# Sheet1.net
KiCad netlist of a schematic drawn in Altium Designer
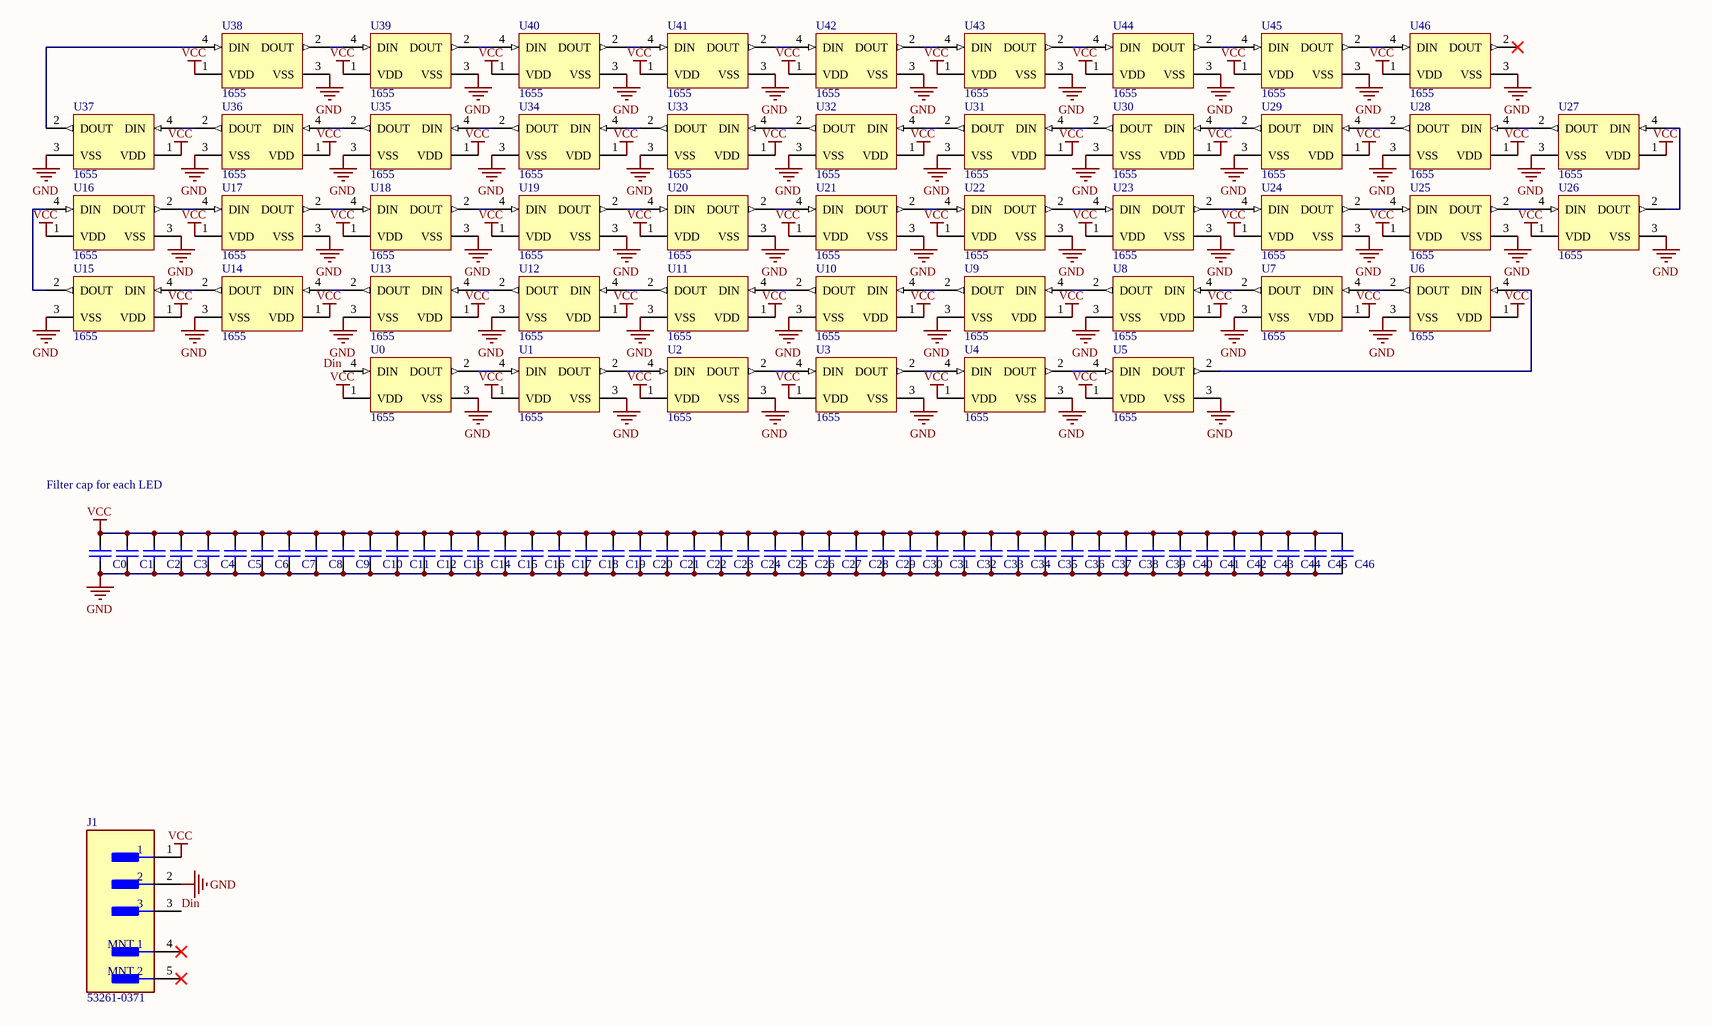
[diagram p0: Sheet1.SchDoc]

(export (version "E")
  (design (tool "Eeschema 10.0.6"))
  (components
    (comp (ref "C0")
      (value "VJ0603Y104JXJAC")
      (footprint "CAPC1608X92X38LL15T08")
      (fields (field (name "MANUFACTURER") "Vitramon"))
      (libsource (lib "Altium Content Vault") (part "CAP"))
    )
    (comp (ref "C1")
      (value "VJ0603Y104JXJAC")
      (footprint "CAPC1608X92X38LL15T08")
      (fields (field (name "MANUFACTURER") "Vitramon"))
      (libsource (lib "Altium Content Vault") (part "CAP"))
    )
    (comp (ref "C2")
      (value "VJ0603Y104JXJAC")
      (footprint "CAPC1608X92X38LL15T08")
      (fields (field (name "MANUFACTURER") "Vitramon"))
      (libsource (lib "Altium Content Vault") (part "CAP"))
    )
    (comp (ref "C3")
      (value "VJ0603Y104JXJAC")
      (footprint "CAPC1608X92X38LL15T08")
      (fields (field (name "MANUFACTURER") "Vitramon"))
      (libsource (lib "Altium Content Vault") (part "CAP"))
    )
    (comp (ref "C4")
      (value "VJ0603Y104JXJAC")
      (footprint "CAPC1608X92X38LL15T08")
      (fields (field (name "MANUFACTURER") "Vitramon"))
      (libsource (lib "Altium Content Vault") (part "CAP"))
    )
    (comp (ref "C5")
      (value "VJ0603Y104JXJAC")
      (footprint "CAPC1608X92X38LL15T08")
      (fields (field (name "MANUFACTURER") "Vitramon"))
      (libsource (lib "Altium Content Vault") (part "CAP"))
    )
    (comp (ref "C6")
      (value "VJ0603Y104JXJAC")
      (footprint "CAPC1608X92X38LL15T08")
      (fields (field (name "MANUFACTURER") "Vitramon"))
      (libsource (lib "Altium Content Vault") (part "CAP"))
    )
    (comp (ref "C7")
      (value "VJ0603Y104JXJAC")
      (footprint "CAPC1608X92X38LL15T08")
      (fields (field (name "MANUFACTURER") "Vitramon"))
      (libsource (lib "Altium Content Vault") (part "CAP"))
    )
    (comp (ref "C8")
      (value "VJ0603Y104JXJAC")
      (footprint "CAPC1608X92X38LL15T08")
      (fields (field (name "MANUFACTURER") "Vitramon"))
      (libsource (lib "Altium Content Vault") (part "CAP"))
    )
    (comp (ref "C9")
      (value "VJ0603Y104JXJAC")
      (footprint "CAPC1608X92X38LL15T08")
      (fields (field (name "MANUFACTURER") "Vitramon"))
      (libsource (lib "Altium Content Vault") (part "CAP"))
    )
    (comp (ref "C10")
      (value "VJ0603Y104JXJAC")
      (footprint "CAPC1608X92X38LL15T08")
      (fields (field (name "MANUFACTURER") "Vitramon"))
      (libsource (lib "Altium Content Vault") (part "CAP"))
    )
    (comp (ref "C11")
      (value "VJ0603Y104JXJAC")
      (footprint "CAPC1608X92X38LL15T08")
      (fields (field (name "MANUFACTURER") "Vitramon"))
      (libsource (lib "Altium Content Vault") (part "CAP"))
    )
    (comp (ref "C12")
      (value "VJ0603Y104JXJAC")
      (footprint "CAPC1608X92X38LL15T08")
      (fields (field (name "MANUFACTURER") "Vitramon"))
      (libsource (lib "Altium Content Vault") (part "CAP"))
    )
    (comp (ref "C13")
      (value "VJ0603Y104JXJAC")
      (footprint "CAPC1608X92X38LL15T08")
      (fields (field (name "MANUFACTURER") "Vitramon"))
      (libsource (lib "Altium Content Vault") (part "CAP"))
    )
    (comp (ref "C14")
      (value "VJ0603Y104JXJAC")
      (footprint "CAPC1608X92X38LL15T08")
      (fields (field (name "MANUFACTURER") "Vitramon"))
      (libsource (lib "Altium Content Vault") (part "CAP"))
    )
    (comp (ref "C15")
      (value "VJ0603Y104JXJAC")
      (footprint "CAPC1608X92X38LL15T08")
      (fields (field (name "MANUFACTURER") "Vitramon"))
      (libsource (lib "Altium Content Vault") (part "CAP"))
    )
    (comp (ref "C16")
      (value "VJ0603Y104JXJAC")
      (footprint "CAPC1608X92X38LL15T08")
      (fields (field (name "MANUFACTURER") "Vitramon"))
      (libsource (lib "Altium Content Vault") (part "CAP"))
    )
    (comp (ref "C17")
      (value "VJ0603Y104JXJAC")
      (footprint "CAPC1608X92X38LL15T08")
      (fields (field (name "MANUFACTURER") "Vitramon"))
      (libsource (lib "Altium Content Vault") (part "CAP"))
    )
    (comp (ref "C18")
      (value "VJ0603Y104JXJAC")
      (footprint "CAPC1608X92X38LL15T08")
      (fields (field (name "MANUFACTURER") "Vitramon"))
      (libsource (lib "Altium Content Vault") (part "CAP"))
    )
    (comp (ref "C19")
      (value "VJ0603Y104JXJAC")
      (footprint "CAPC1608X92X38LL15T08")
      (fields (field (name "MANUFACTURER") "Vitramon"))
      (libsource (lib "Altium Content Vault") (part "CAP"))
    )
    (comp (ref "C20")
      (value "VJ0603Y104JXJAC")
      (footprint "CAPC1608X92X38LL15T08")
      (fields (field (name "MANUFACTURER") "Vitramon"))
      (libsource (lib "Altium Content Vault") (part "CAP"))
    )
    (comp (ref "C21")
      (value "VJ0603Y104JXJAC")
      (footprint "CAPC1608X92X38LL15T08")
      (fields (field (name "MANUFACTURER") "Vitramon"))
      (libsource (lib "Altium Content Vault") (part "CAP"))
    )
    (comp (ref "C22")
      (value "VJ0603Y104JXJAC")
      (footprint "CAPC1608X92X38LL15T08")
      (fields (field (name "MANUFACTURER") "Vitramon"))
      (libsource (lib "Altium Content Vault") (part "CAP"))
    )
    (comp (ref "C23")
      (value "VJ0603Y104JXJAC")
      (footprint "CAPC1608X92X38LL15T08")
      (fields (field (name "MANUFACTURER") "Vitramon"))
      (libsource (lib "Altium Content Vault") (part "CAP"))
    )
    (comp (ref "C24")
      (value "VJ0603Y104JXJAC")
      (footprint "CAPC1608X92X38LL15T08")
      (fields (field (name "MANUFACTURER") "Vitramon"))
      (libsource (lib "Altium Content Vault") (part "CAP"))
    )
    (comp (ref "C25")
      (value "VJ0603Y104JXJAC")
      (footprint "CAPC1608X92X38LL15T08")
      (fields (field (name "MANUFACTURER") "Vitramon"))
      (libsource (lib "Altium Content Vault") (part "CAP"))
    )
    (comp (ref "C26")
      (value "VJ0603Y104JXJAC")
      (footprint "CAPC1608X92X38LL15T08")
      (fields (field (name "MANUFACTURER") "Vitramon"))
      (libsource (lib "Altium Content Vault") (part "CAP"))
    )
    (comp (ref "C27")
      (value "VJ0603Y104JXJAC")
      (footprint "CAPC1608X92X38LL15T08")
      (fields (field (name "MANUFACTURER") "Vitramon"))
      (libsource (lib "Altium Content Vault") (part "CAP"))
    )
    (comp (ref "C28")
      (value "VJ0603Y104JXJAC")
      (footprint "CAPC1608X92X38LL15T08")
      (fields (field (name "MANUFACTURER") "Vitramon"))
      (libsource (lib "Altium Content Vault") (part "CAP"))
    )
    (comp (ref "C29")
      (value "VJ0603Y104JXJAC")
      (footprint "CAPC1608X92X38LL15T08")
      (fields (field (name "MANUFACTURER") "Vitramon"))
      (libsource (lib "Altium Content Vault") (part "CAP"))
    )
    (comp (ref "C30")
      (value "VJ0603Y104JXJAC")
      (footprint "CAPC1608X92X38LL15T08")
      (fields (field (name "MANUFACTURER") "Vitramon"))
      (libsource (lib "Altium Content Vault") (part "CAP"))
    )
    (comp (ref "C31")
      (value "VJ0603Y104JXJAC")
      (footprint "CAPC1608X92X38LL15T08")
      (fields (field (name "MANUFACTURER") "Vitramon"))
      (libsource (lib "Altium Content Vault") (part "CAP"))
    )
    (comp (ref "C32")
      (value "VJ0603Y104JXJAC")
      (footprint "CAPC1608X92X38LL15T08")
      (fields (field (name "MANUFACTURER") "Vitramon"))
      (libsource (lib "Altium Content Vault") (part "CAP"))
    )
    (comp (ref "C33")
      (value "VJ0603Y104JXJAC")
      (footprint "CAPC1608X92X38LL15T08")
      (fields (field (name "MANUFACTURER") "Vitramon"))
      (libsource (lib "Altium Content Vault") (part "CAP"))
    )
    (comp (ref "C34")
      (value "VJ0603Y104JXJAC")
      (footprint "CAPC1608X92X38LL15T08")
      (fields (field (name "MANUFACTURER") "Vitramon"))
      (libsource (lib "Altium Content Vault") (part "CAP"))
    )
    (comp (ref "C35")
      (value "VJ0603Y104JXJAC")
      (footprint "CAPC1608X92X38LL15T08")
      (fields (field (name "MANUFACTURER") "Vitramon"))
      (libsource (lib "Altium Content Vault") (part "CAP"))
    )
    (comp (ref "C36")
      (value "VJ0603Y104JXJAC")
      (footprint "CAPC1608X92X38LL15T08")
      (fields (field (name "MANUFACTURER") "Vitramon"))
      (libsource (lib "Altium Content Vault") (part "CAP"))
    )
    (comp (ref "C37")
      (value "VJ0603Y104JXJAC")
      (footprint "CAPC1608X92X38LL15T08")
      (fields (field (name "MANUFACTURER") "Vitramon"))
      (libsource (lib "Altium Content Vault") (part "CAP"))
    )
    (comp (ref "C38")
      (value "VJ0603Y104JXJAC")
      (footprint "CAPC1608X92X38LL15T08")
      (fields (field (name "MANUFACTURER") "Vitramon"))
      (libsource (lib "Altium Content Vault") (part "CAP"))
    )
    (comp (ref "C39")
      (value "VJ0603Y104JXJAC")
      (footprint "CAPC1608X92X38LL15T08")
      (fields (field (name "MANUFACTURER") "Vitramon"))
      (libsource (lib "Altium Content Vault") (part "CAP"))
    )
    (comp (ref "C40")
      (value "VJ0603Y104JXJAC")
      (footprint "CAPC1608X92X38LL15T08")
      (fields (field (name "MANUFACTURER") "Vitramon"))
      (libsource (lib "Altium Content Vault") (part "CAP"))
    )
    (comp (ref "C41")
      (value "VJ0603Y104JXJAC")
      (footprint "CAPC1608X92X38LL15T08")
      (fields (field (name "MANUFACTURER") "Vitramon"))
      (libsource (lib "Altium Content Vault") (part "CAP"))
    )
    (comp (ref "C42")
      (value "VJ0603Y104JXJAC")
      (footprint "CAPC1608X92X38LL15T08")
      (fields (field (name "MANUFACTURER") "Vitramon"))
      (libsource (lib "Altium Content Vault") (part "CAP"))
    )
    (comp (ref "C43")
      (value "VJ0603Y104JXJAC")
      (footprint "CAPC1608X92X38LL15T08")
      (fields (field (name "MANUFACTURER") "Vitramon"))
      (libsource (lib "Altium Content Vault") (part "CAP"))
    )
    (comp (ref "C44")
      (value "VJ0603Y104JXJAC")
      (footprint "CAPC1608X92X38LL15T08")
      (fields (field (name "MANUFACTURER") "Vitramon"))
      (libsource (lib "Altium Content Vault") (part "CAP"))
    )
    (comp (ref "C45")
      (value "VJ0603Y104JXJAC")
      (footprint "CAPC1608X92X38LL15T08")
      (fields (field (name "MANUFACTURER") "Vitramon"))
      (libsource (lib "Altium Content Vault") (part "CAP"))
    )
    (comp (ref "C46")
      (value "VJ0603Y104JXJAC")
      (footprint "CAPC1608X92X38LL15T08")
      (fields (field (name "MANUFACTURER") "Vitramon"))
      (libsource (lib "Altium Content Vault") (part "CAP"))
    )
    (comp (ref "J1")
      (value "53261-0371")
      (footprint "FP-53261-0371-MFG")
      (description "CONN HEADER SMD R/A 3POS 1.25MM")
      (fields
        (field (name "MANUFACTURER") "Molex")
        (field (name "OCTOPART") "https://octopart.com/53261-0371-molex-655314")
      )
      (libsource (lib "Altium Content Vault") (part "13850a6865a90496d8e6d51657cef87"))
    )
    (comp (ref "U0")
      (value "1655")
      (footprint "ADA-RGB-1655_V")
      (fields (field (name "MANUFACTURER") "Adafruit-Industries-LLC"))
      (libsource (lib "") (part "ADA-RGB-1655-4_1"))
    )
    (comp (ref "U1")
      (value "1655")
      (footprint "ADA-RGB-1655_V")
      (fields (field (name "MANUFACTURER") "Adafruit-Industries-LLC"))
      (libsource (lib "") (part "ADA-RGB-1655-4_1"))
    )
    (comp (ref "U2")
      (value "1655")
      (footprint "ADA-RGB-1655_V")
      (fields (field (name "MANUFACTURER") "Adafruit-Industries-LLC"))
      (libsource (lib "") (part "ADA-RGB-1655-4_1"))
    )
    (comp (ref "U3")
      (value "1655")
      (footprint "ADA-RGB-1655_V")
      (fields (field (name "MANUFACTURER") "Adafruit-Industries-LLC"))
      (libsource (lib "") (part "ADA-RGB-1655-4_1"))
    )
    (comp (ref "U4")
      (value "1655")
      (footprint "ADA-RGB-1655_V")
      (fields (field (name "MANUFACTURER") "Adafruit-Industries-LLC"))
      (libsource (lib "") (part "ADA-RGB-1655-4_1"))
    )
    (comp (ref "U5")
      (value "1655")
      (footprint "ADA-RGB-1655_V")
      (fields (field (name "MANUFACTURER") "Adafruit-Industries-LLC"))
      (libsource (lib "") (part "ADA-RGB-1655-4_1"))
    )
    (comp (ref "U6")
      (value "1655")
      (footprint "ADA-RGB-1655_V")
      (fields (field (name "MANUFACTURER") "Adafruit-Industries-LLC"))
      (libsource (lib "Altium Content Vault") (part "ADA-RGB-1655-4"))
    )
    (comp (ref "U7")
      (value "1655")
      (footprint "ADA-RGB-1655_V")
      (fields (field (name "MANUFACTURER") "Adafruit-Industries-LLC"))
      (libsource (lib "Altium Content Vault") (part "ADA-RGB-1655-4"))
    )
    (comp (ref "U8")
      (value "1655")
      (footprint "ADA-RGB-1655_V")
      (fields (field (name "MANUFACTURER") "Adafruit-Industries-LLC"))
      (libsource (lib "Altium Content Vault") (part "ADA-RGB-1655-4"))
    )
    (comp (ref "U9")
      (value "1655")
      (footprint "ADA-RGB-1655_V")
      (fields (field (name "MANUFACTURER") "Adafruit-Industries-LLC"))
      (libsource (lib "Altium Content Vault") (part "ADA-RGB-1655-4"))
    )
    (comp (ref "U10")
      (value "1655")
      (footprint "ADA-RGB-1655_V")
      (fields (field (name "MANUFACTURER") "Adafruit-Industries-LLC"))
      (libsource (lib "Altium Content Vault") (part "ADA-RGB-1655-4"))
    )
    (comp (ref "U11")
      (value "1655")
      (footprint "ADA-RGB-1655_V")
      (fields (field (name "MANUFACTURER") "Adafruit-Industries-LLC"))
      (libsource (lib "Altium Content Vault") (part "ADA-RGB-1655-4"))
    )
    (comp (ref "U12")
      (value "1655")
      (footprint "ADA-RGB-1655_V")
      (fields (field (name "MANUFACTURER") "Adafruit-Industries-LLC"))
      (libsource (lib "Altium Content Vault") (part "ADA-RGB-1655-4"))
    )
    (comp (ref "U13")
      (value "1655")
      (footprint "ADA-RGB-1655_V")
      (fields (field (name "MANUFACTURER") "Adafruit-Industries-LLC"))
      (libsource (lib "Altium Content Vault") (part "ADA-RGB-1655-4"))
    )
    (comp (ref "U14")
      (value "1655")
      (footprint "ADA-RGB-1655_V")
      (fields (field (name "MANUFACTURER") "Adafruit-Industries-LLC"))
      (libsource (lib "Altium Content Vault") (part "ADA-RGB-1655-4"))
    )
    (comp (ref "U15")
      (value "1655")
      (footprint "ADA-RGB-1655_V")
      (fields (field (name "MANUFACTURER") "Adafruit-Industries-LLC"))
      (libsource (lib "Altium Content Vault") (part "ADA-RGB-1655-4"))
    )
    (comp (ref "U16")
      (value "1655")
      (footprint "ADA-RGB-1655_V")
      (fields (field (name "MANUFACTURER") "Adafruit-Industries-LLC"))
      (libsource (lib "") (part "ADA-RGB-1655-4_1"))
    )
    (comp (ref "U17")
      (value "1655")
      (footprint "ADA-RGB-1655_V")
      (fields (field (name "MANUFACTURER") "Adafruit-Industries-LLC"))
      (libsource (lib "") (part "ADA-RGB-1655-4_1"))
    )
    (comp (ref "U18")
      (value "1655")
      (footprint "ADA-RGB-1655_V")
      (fields (field (name "MANUFACTURER") "Adafruit-Industries-LLC"))
      (libsource (lib "") (part "ADA-RGB-1655-4_1"))
    )
    (comp (ref "U19")
      (value "1655")
      (footprint "ADA-RGB-1655_V")
      (fields (field (name "MANUFACTURER") "Adafruit-Industries-LLC"))
      (libsource (lib "") (part "ADA-RGB-1655-4_1"))
    )
    (comp (ref "U20")
      (value "1655")
      (footprint "ADA-RGB-1655_V")
      (fields (field (name "MANUFACTURER") "Adafruit-Industries-LLC"))
      (libsource (lib "") (part "ADA-RGB-1655-4_1"))
    )
    (comp (ref "U21")
      (value "1655")
      (footprint "ADA-RGB-1655_V")
      (fields (field (name "MANUFACTURER") "Adafruit-Industries-LLC"))
      (libsource (lib "") (part "ADA-RGB-1655-4_1"))
    )
    (comp (ref "U22")
      (value "1655")
      (footprint "ADA-RGB-1655_V")
      (fields (field (name "MANUFACTURER") "Adafruit-Industries-LLC"))
      (libsource (lib "") (part "ADA-RGB-1655-4_1"))
    )
    (comp (ref "U23")
      (value "1655")
      (footprint "ADA-RGB-1655_V")
      (fields (field (name "MANUFACTURER") "Adafruit-Industries-LLC"))
      (libsource (lib "") (part "ADA-RGB-1655-4_1"))
    )
    (comp (ref "U24")
      (value "1655")
      (footprint "ADA-RGB-1655_V")
      (fields (field (name "MANUFACTURER") "Adafruit-Industries-LLC"))
      (libsource (lib "") (part "ADA-RGB-1655-4_1"))
    )
    (comp (ref "U25")
      (value "1655")
      (footprint "ADA-RGB-1655_V")
      (fields (field (name "MANUFACTURER") "Adafruit-Industries-LLC"))
      (libsource (lib "") (part "ADA-RGB-1655-4_1"))
    )
    (comp (ref "U26")
      (value "1655")
      (footprint "ADA-RGB-1655_V")
      (fields (field (name "MANUFACTURER") "Adafruit-Industries-LLC"))
      (libsource (lib "") (part "ADA-RGB-1655-4_1"))
    )
    (comp (ref "U27")
      (value "1655")
      (footprint "ADA-RGB-1655_V")
      (fields (field (name "MANUFACTURER") "Adafruit-Industries-LLC"))
      (libsource (lib "Altium Content Vault") (part "ADA-RGB-1655-4"))
    )
    (comp (ref "U28")
      (value "1655")
      (footprint "ADA-RGB-1655_V")
      (fields (field (name "MANUFACTURER") "Adafruit-Industries-LLC"))
      (libsource (lib "Altium Content Vault") (part "ADA-RGB-1655-4"))
    )
    (comp (ref "U29")
      (value "1655")
      (footprint "ADA-RGB-1655_V")
      (fields (field (name "MANUFACTURER") "Adafruit-Industries-LLC"))
      (libsource (lib "Altium Content Vault") (part "ADA-RGB-1655-4"))
    )
    (comp (ref "U30")
      (value "1655")
      (footprint "ADA-RGB-1655_V")
      (fields (field (name "MANUFACTURER") "Adafruit-Industries-LLC"))
      (libsource (lib "Altium Content Vault") (part "ADA-RGB-1655-4"))
    )
    (comp (ref "U31")
      (value "1655")
      (footprint "ADA-RGB-1655_V")
      (fields (field (name "MANUFACTURER") "Adafruit-Industries-LLC"))
      (libsource (lib "Altium Content Vault") (part "ADA-RGB-1655-4"))
    )
    (comp (ref "U32")
      (value "1655")
      (footprint "ADA-RGB-1655_V")
      (fields (field (name "MANUFACTURER") "Adafruit-Industries-LLC"))
      (libsource (lib "Altium Content Vault") (part "ADA-RGB-1655-4"))
    )
    (comp (ref "U33")
      (value "1655")
      (footprint "ADA-RGB-1655_V")
      (fields (field (name "MANUFACTURER") "Adafruit-Industries-LLC"))
      (libsource (lib "Altium Content Vault") (part "ADA-RGB-1655-4"))
    )
    (comp (ref "U34")
      (value "1655")
      (footprint "ADA-RGB-1655_V")
      (fields (field (name "MANUFACTURER") "Adafruit-Industries-LLC"))
      (libsource (lib "Altium Content Vault") (part "ADA-RGB-1655-4"))
    )
    (comp (ref "U35")
      (value "1655")
      (footprint "ADA-RGB-1655_V")
      (fields (field (name "MANUFACTURER") "Adafruit-Industries-LLC"))
      (libsource (lib "Altium Content Vault") (part "ADA-RGB-1655-4"))
    )
    (comp (ref "U36")
      (value "1655")
      (footprint "ADA-RGB-1655_V")
      (fields (field (name "MANUFACTURER") "Adafruit-Industries-LLC"))
      (libsource (lib "Altium Content Vault") (part "ADA-RGB-1655-4"))
    )
    (comp (ref "U37")
      (value "1655")
      (footprint "ADA-RGB-1655_V")
      (fields (field (name "MANUFACTURER") "Adafruit-Industries-LLC"))
      (libsource (lib "Altium Content Vault") (part "ADA-RGB-1655-4"))
    )
    (comp (ref "U38")
      (value "1655")
      (footprint "ADA-RGB-1655_V")
      (fields (field (name "MANUFACTURER") "Adafruit-Industries-LLC"))
      (libsource (lib "") (part "ADA-RGB-1655-4_1"))
    )
    (comp (ref "U39")
      (value "1655")
      (footprint "ADA-RGB-1655_V")
      (fields (field (name "MANUFACTURER") "Adafruit-Industries-LLC"))
      (libsource (lib "") (part "ADA-RGB-1655-4_1"))
    )
    (comp (ref "U40")
      (value "1655")
      (footprint "ADA-RGB-1655_V")
      (fields (field (name "MANUFACTURER") "Adafruit-Industries-LLC"))
      (libsource (lib "") (part "ADA-RGB-1655-4_1"))
    )
    (comp (ref "U41")
      (value "1655")
      (footprint "ADA-RGB-1655_V")
      (fields (field (name "MANUFACTURER") "Adafruit-Industries-LLC"))
      (libsource (lib "") (part "ADA-RGB-1655-4_1"))
    )
    (comp (ref "U42")
      (value "1655")
      (footprint "ADA-RGB-1655_V")
      (fields (field (name "MANUFACTURER") "Adafruit-Industries-LLC"))
      (libsource (lib "") (part "ADA-RGB-1655-4_1"))
    )
    (comp (ref "U43")
      (value "1655")
      (footprint "ADA-RGB-1655_V")
      (fields (field (name "MANUFACTURER") "Adafruit-Industries-LLC"))
      (libsource (lib "") (part "ADA-RGB-1655-4_1"))
    )
    (comp (ref "U44")
      (value "1655")
      (footprint "ADA-RGB-1655_V")
      (fields (field (name "MANUFACTURER") "Adafruit-Industries-LLC"))
      (libsource (lib "") (part "ADA-RGB-1655-4_1"))
    )
    (comp (ref "U45")
      (value "1655")
      (footprint "ADA-RGB-1655_V")
      (fields (field (name "MANUFACTURER") "Adafruit-Industries-LLC"))
      (libsource (lib "") (part "ADA-RGB-1655-4_1"))
    )
    (comp (ref "U46")
      (value "1655")
      (footprint "ADA-RGB-1655_V")
      (fields (field (name "MANUFACTURER") "Adafruit-Industries-LLC"))
      (libsource (lib "") (part "ADA-RGB-1655-4_1"))
    )
  )
  (nets
    (net (code "1") (name "/Din") (class "Default")
      (node (ref "J1") (pin "3") (pinfunction "3_3") (pintype "passive"))
      (node (ref "U0") (pin "4") (pinfunction "DIN_4") (pintype "input"))
    )
    (net (code "2") (name "GND") (class "Default")
      (node (ref "C0") (pin "2") (pinfunction "2_2") (pintype "passive"))
      (node (ref "C1") (pin "2") (pinfunction "2_2") (pintype "passive"))
      (node (ref "C10") (pin "2") (pinfunction "2_2") (pintype "passive"))
      (node (ref "C11") (pin "2") (pinfunction "2_2") (pintype "passive"))
      (node (ref "C12") (pin "2") (pinfunction "2_2") (pintype "passive"))
      (node (ref "C13") (pin "2") (pinfunction "2_2") (pintype "passive"))
      (node (ref "C14") (pin "2") (pinfunction "2_2") (pintype "passive"))
      (node (ref "C15") (pin "2") (pinfunction "2_2") (pintype "passive"))
      (node (ref "C16") (pin "2") (pinfunction "2_2") (pintype "passive"))
      (node (ref "C17") (pin "2") (pinfunction "2_2") (pintype "passive"))
      (node (ref "C18") (pin "2") (pinfunction "2_2") (pintype "passive"))
      (node (ref "C19") (pin "2") (pinfunction "2_2") (pintype "passive"))
      (node (ref "C2") (pin "2") (pinfunction "2_2") (pintype "passive"))
      (node (ref "C20") (pin "2") (pinfunction "2_2") (pintype "passive"))
      (node (ref "C21") (pin "2") (pinfunction "2_2") (pintype "passive"))
      (node (ref "C22") (pin "2") (pinfunction "2_2") (pintype "passive"))
      (node (ref "C23") (pin "2") (pinfunction "2_2") (pintype "passive"))
      (node (ref "C24") (pin "2") (pinfunction "2_2") (pintype "passive"))
      (node (ref "C25") (pin "2") (pinfunction "2_2") (pintype "passive"))
      (node (ref "C26") (pin "2") (pinfunction "2_2") (pintype "passive"))
      (node (ref "C27") (pin "2") (pinfunction "2_2") (pintype "passive"))
      (node (ref "C28") (pin "2") (pinfunction "2_2") (pintype "passive"))
      (node (ref "C29") (pin "2") (pinfunction "2_2") (pintype "passive"))
      (node (ref "C3") (pin "2") (pinfunction "2_2") (pintype "passive"))
      (node (ref "C30") (pin "2") (pinfunction "2_2") (pintype "passive"))
      (node (ref "C31") (pin "2") (pinfunction "2_2") (pintype "passive"))
      (node (ref "C32") (pin "2") (pinfunction "2_2") (pintype "passive"))
      (node (ref "C33") (pin "2") (pinfunction "2_2") (pintype "passive"))
      (node (ref "C34") (pin "2") (pinfunction "2_2") (pintype "passive"))
      (node (ref "C35") (pin "2") (pinfunction "2_2") (pintype "passive"))
      (node (ref "C36") (pin "2") (pinfunction "2_2") (pintype "passive"))
      (node (ref "C37") (pin "2") (pinfunction "2_2") (pintype "passive"))
      (node (ref "C38") (pin "2") (pinfunction "2_2") (pintype "passive"))
      (node (ref "C39") (pin "2") (pinfunction "2_2") (pintype "passive"))
      (node (ref "C4") (pin "2") (pinfunction "2_2") (pintype "passive"))
      (node (ref "C40") (pin "2") (pinfunction "2_2") (pintype "passive"))
      (node (ref "C41") (pin "2") (pinfunction "2_2") (pintype "passive"))
      (node (ref "C42") (pin "2") (pinfunction "2_2") (pintype "passive"))
      (node (ref "C43") (pin "2") (pinfunction "2_2") (pintype "passive"))
      (node (ref "C44") (pin "2") (pinfunction "2_2") (pintype "passive"))
      (node (ref "C45") (pin "2") (pinfunction "2_2") (pintype "passive"))
      (node (ref "C46") (pin "2") (pinfunction "2_2") (pintype "passive"))
      (node (ref "C5") (pin "2") (pinfunction "2_2") (pintype "passive"))
      (node (ref "C6") (pin "2") (pinfunction "2_2") (pintype "passive"))
      (node (ref "C7") (pin "2") (pinfunction "2_2") (pintype "passive"))
      (node (ref "C8") (pin "2") (pinfunction "2_2") (pintype "passive"))
      (node (ref "C9") (pin "2") (pinfunction "2_2") (pintype "passive"))
      (node (ref "J1") (pin "2") (pinfunction "2_2") (pintype "passive"))
      (node (ref "U0") (pin "3") (pinfunction "VSS_3") (pintype "power_in"))
      (node (ref "U1") (pin "3") (pinfunction "VSS_3") (pintype "power_in"))
      (node (ref "U10") (pin "3") (pinfunction "VSS_3") (pintype "power_in"))
      (node (ref "U11") (pin "3") (pinfunction "VSS_3") (pintype "power_in"))
      (node (ref "U12") (pin "3") (pinfunction "VSS_3") (pintype "power_in"))
      (node (ref "U13") (pin "3") (pinfunction "VSS_3") (pintype "power_in"))
      (node (ref "U14") (pin "3") (pinfunction "VSS_3") (pintype "power_in"))
      (node (ref "U15") (pin "3") (pinfunction "VSS_3") (pintype "power_in"))
      (node (ref "U16") (pin "3") (pinfunction "VSS_3") (pintype "power_in"))
      (node (ref "U17") (pin "3") (pinfunction "VSS_3") (pintype "power_in"))
      (node (ref "U18") (pin "3") (pinfunction "VSS_3") (pintype "power_in"))
      (node (ref "U19") (pin "3") (pinfunction "VSS_3") (pintype "power_in"))
      (node (ref "U2") (pin "3") (pinfunction "VSS_3") (pintype "power_in"))
      (node (ref "U20") (pin "3") (pinfunction "VSS_3") (pintype "power_in"))
      (node (ref "U21") (pin "3") (pinfunction "VSS_3") (pintype "power_in"))
      (node (ref "U22") (pin "3") (pinfunction "VSS_3") (pintype "power_in"))
      (node (ref "U23") (pin "3") (pinfunction "VSS_3") (pintype "power_in"))
      (node (ref "U24") (pin "3") (pinfunction "VSS_3") (pintype "power_in"))
      (node (ref "U25") (pin "3") (pinfunction "VSS_3") (pintype "power_in"))
      (node (ref "U26") (pin "3") (pinfunction "VSS_3") (pintype "power_in"))
      (node (ref "U27") (pin "3") (pinfunction "VSS_3") (pintype "power_in"))
      (node (ref "U28") (pin "3") (pinfunction "VSS_3") (pintype "power_in"))
      (node (ref "U29") (pin "3") (pinfunction "VSS_3") (pintype "power_in"))
      (node (ref "U3") (pin "3") (pinfunction "VSS_3") (pintype "power_in"))
      (node (ref "U30") (pin "3") (pinfunction "VSS_3") (pintype "power_in"))
      (node (ref "U31") (pin "3") (pinfunction "VSS_3") (pintype "power_in"))
      (node (ref "U32") (pin "3") (pinfunction "VSS_3") (pintype "power_in"))
      (node (ref "U33") (pin "3") (pinfunction "VSS_3") (pintype "power_in"))
      (node (ref "U34") (pin "3") (pinfunction "VSS_3") (pintype "power_in"))
      (node (ref "U35") (pin "3") (pinfunction "VSS_3") (pintype "power_in"))
      (node (ref "U36") (pin "3") (pinfunction "VSS_3") (pintype "power_in"))
      (node (ref "U37") (pin "3") (pinfunction "VSS_3") (pintype "power_in"))
      (node (ref "U38") (pin "3") (pinfunction "VSS_3") (pintype "power_in"))
      (node (ref "U39") (pin "3") (pinfunction "VSS_3") (pintype "power_in"))
      (node (ref "U4") (pin "3") (pinfunction "VSS_3") (pintype "power_in"))
      (node (ref "U40") (pin "3") (pinfunction "VSS_3") (pintype "power_in"))
      (node (ref "U41") (pin "3") (pinfunction "VSS_3") (pintype "power_in"))
      (node (ref "U42") (pin "3") (pinfunction "VSS_3") (pintype "power_in"))
      (node (ref "U43") (pin "3") (pinfunction "VSS_3") (pintype "power_in"))
      (node (ref "U44") (pin "3") (pinfunction "VSS_3") (pintype "power_in"))
      (node (ref "U45") (pin "3") (pinfunction "VSS_3") (pintype "power_in"))
      (node (ref "U46") (pin "3") (pinfunction "VSS_3") (pintype "power_in"))
      (node (ref "U5") (pin "3") (pinfunction "VSS_3") (pintype "power_in"))
      (node (ref "U6") (pin "3") (pinfunction "VSS_3") (pintype "power_in"))
      (node (ref "U7") (pin "3") (pinfunction "VSS_3") (pintype "power_in"))
      (node (ref "U8") (pin "3") (pinfunction "VSS_3") (pintype "power_in"))
      (node (ref "U9") (pin "3") (pinfunction "VSS_3") (pintype "power_in"))
    )
    (net (code "3") (name "Net-(U0-DOUT)") (class "Default")
      (node (ref "U0") (pin "2") (pinfunction "DOUT_2") (pintype "output"))
      (node (ref "U1") (pin "4") (pinfunction "DIN_4") (pintype "input"))
    )
    (net (code "4") (name "Net-(U1-DOUT)") (class "Default")
      (node (ref "U1") (pin "2") (pinfunction "DOUT_2") (pintype "output"))
      (node (ref "U2") (pin "4") (pinfunction "DIN_4") (pintype "input"))
    )
    (net (code "5") (name "Net-(U2-DOUT)") (class "Default")
      (node (ref "U2") (pin "2") (pinfunction "DOUT_2") (pintype "output"))
      (node (ref "U3") (pin "4") (pinfunction "DIN_4") (pintype "input"))
    )
    (net (code "6") (name "Net-(U3-DOUT)") (class "Default")
      (node (ref "U3") (pin "2") (pinfunction "DOUT_2") (pintype "output"))
      (node (ref "U4") (pin "4") (pinfunction "DIN_4") (pintype "input"))
    )
    (net (code "7") (name "Net-(U4-DOUT)") (class "Default")
      (node (ref "U4") (pin "2") (pinfunction "DOUT_2") (pintype "output"))
      (node (ref "U5") (pin "4") (pinfunction "DIN_4") (pintype "input"))
    )
    (net (code "8") (name "Net-(U5-DOUT)") (class "Default")
      (node (ref "U5") (pin "2") (pinfunction "DOUT_2") (pintype "output"))
      (node (ref "U6") (pin "4") (pinfunction "DIN_4") (pintype "input"))
    )
    (net (code "9") (name "Net-(U6-DOUT)") (class "Default")
      (node (ref "U6") (pin "2") (pinfunction "DOUT_2") (pintype "output"))
      (node (ref "U7") (pin "4") (pinfunction "DIN_4") (pintype "input"))
    )
    (net (code "10") (name "Net-(U7-DOUT)") (class "Default")
      (node (ref "U7") (pin "2") (pinfunction "DOUT_2") (pintype "output"))
      (node (ref "U8") (pin "4") (pinfunction "DIN_4") (pintype "input"))
    )
    (net (code "11") (name "Net-(U8-DOUT)") (class "Default")
      (node (ref "U8") (pin "2") (pinfunction "DOUT_2") (pintype "output"))
      (node (ref "U9") (pin "4") (pinfunction "DIN_4") (pintype "input"))
    )
    (net (code "12") (name "Net-(U10-DIN)") (class "Default")
      (node (ref "U10") (pin "4") (pinfunction "DIN_4") (pintype "input"))
      (node (ref "U9") (pin "2") (pinfunction "DOUT_2") (pintype "output"))
    )
    (net (code "13") (name "Net-(U10-DOUT)") (class "Default")
      (node (ref "U10") (pin "2") (pinfunction "DOUT_2") (pintype "output"))
      (node (ref "U11") (pin "4") (pinfunction "DIN_4") (pintype "input"))
    )
    (net (code "14") (name "Net-(U11-DOUT)") (class "Default")
      (node (ref "U11") (pin "2") (pinfunction "DOUT_2") (pintype "output"))
      (node (ref "U12") (pin "4") (pinfunction "DIN_4") (pintype "input"))
    )
    (net (code "15") (name "Net-(U12-DOUT)") (class "Default")
      (node (ref "U12") (pin "2") (pinfunction "DOUT_2") (pintype "output"))
      (node (ref "U13") (pin "4") (pinfunction "DIN_4") (pintype "input"))
    )
    (net (code "16") (name "Net-(U13-DOUT)") (class "Default")
      (node (ref "U13") (pin "2") (pinfunction "DOUT_2") (pintype "output"))
      (node (ref "U14") (pin "4") (pinfunction "DIN_4") (pintype "input"))
    )
    (net (code "17") (name "Net-(U14-DOUT)") (class "Default")
      (node (ref "U14") (pin "2") (pinfunction "DOUT_2") (pintype "output"))
      (node (ref "U15") (pin "4") (pinfunction "DIN_4") (pintype "input"))
    )
    (net (code "18") (name "Net-(U15-DOUT)") (class "Default")
      (node (ref "U15") (pin "2") (pinfunction "DOUT_2") (pintype "output"))
      (node (ref "U16") (pin "4") (pinfunction "DIN_4") (pintype "input"))
    )
    (net (code "19") (name "Net-(U16-DOUT)") (class "Default")
      (node (ref "U16") (pin "2") (pinfunction "DOUT_2") (pintype "output"))
      (node (ref "U17") (pin "4") (pinfunction "DIN_4") (pintype "input"))
    )
    (net (code "20") (name "Net-(U17-DOUT)") (class "Default")
      (node (ref "U17") (pin "2") (pinfunction "DOUT_2") (pintype "output"))
      (node (ref "U18") (pin "4") (pinfunction "DIN_4") (pintype "input"))
    )
    (net (code "21") (name "Net-(U18-DOUT)") (class "Default")
      (node (ref "U18") (pin "2") (pinfunction "DOUT_2") (pintype "output"))
      (node (ref "U19") (pin "4") (pinfunction "DIN_4") (pintype "input"))
    )
    (net (code "22") (name "Net-(U19-DOUT)") (class "Default")
      (node (ref "U19") (pin "2") (pinfunction "DOUT_2") (pintype "output"))
      (node (ref "U20") (pin "4") (pinfunction "DIN_4") (pintype "input"))
    )
    (net (code "23") (name "Net-(U20-DOUT)") (class "Default")
      (node (ref "U20") (pin "2") (pinfunction "DOUT_2") (pintype "output"))
      (node (ref "U21") (pin "4") (pinfunction "DIN_4") (pintype "input"))
    )
    (net (code "24") (name "Net-(U21-DOUT)") (class "Default")
      (node (ref "U21") (pin "2") (pinfunction "DOUT_2") (pintype "output"))
      (node (ref "U22") (pin "4") (pinfunction "DIN_4") (pintype "input"))
    )
    (net (code "25") (name "Net-(U22-DOUT)") (class "Default")
      (node (ref "U22") (pin "2") (pinfunction "DOUT_2") (pintype "output"))
      (node (ref "U23") (pin "4") (pinfunction "DIN_4") (pintype "input"))
    )
    (net (code "26") (name "Net-(U23-DOUT)") (class "Default")
      (node (ref "U23") (pin "2") (pinfunction "DOUT_2") (pintype "output"))
      (node (ref "U24") (pin "4") (pinfunction "DIN_4") (pintype "input"))
    )
    (net (code "27") (name "Net-(U24-DOUT)") (class "Default")
      (node (ref "U24") (pin "2") (pinfunction "DOUT_2") (pintype "output"))
      (node (ref "U25") (pin "4") (pinfunction "DIN_4") (pintype "input"))
    )
    (net (code "28") (name "Net-(U25-DOUT)") (class "Default")
      (node (ref "U25") (pin "2") (pinfunction "DOUT_2") (pintype "output"))
      (node (ref "U26") (pin "4") (pinfunction "DIN_4") (pintype "input"))
    )
    (net (code "29") (name "Net-(U26-DOUT)") (class "Default")
      (node (ref "U26") (pin "2") (pinfunction "DOUT_2") (pintype "output"))
      (node (ref "U27") (pin "4") (pinfunction "DIN_4") (pintype "input"))
    )
    (net (code "30") (name "Net-(U27-DOUT)") (class "Default")
      (node (ref "U27") (pin "2") (pinfunction "DOUT_2") (pintype "output"))
      (node (ref "U28") (pin "4") (pinfunction "DIN_4") (pintype "input"))
    )
    (net (code "31") (name "Net-(U28-DOUT)") (class "Default")
      (node (ref "U28") (pin "2") (pinfunction "DOUT_2") (pintype "output"))
      (node (ref "U29") (pin "4") (pinfunction "DIN_4") (pintype "input"))
    )
    (net (code "32") (name "Net-(U29-DOUT)") (class "Default")
      (node (ref "U29") (pin "2") (pinfunction "DOUT_2") (pintype "output"))
      (node (ref "U30") (pin "4") (pinfunction "DIN_4") (pintype "input"))
    )
    (net (code "33") (name "Net-(U30-DOUT)") (class "Default")
      (node (ref "U30") (pin "2") (pinfunction "DOUT_2") (pintype "output"))
      (node (ref "U31") (pin "4") (pinfunction "DIN_4") (pintype "input"))
    )
    (net (code "34") (name "Net-(U31-DOUT)") (class "Default")
      (node (ref "U31") (pin "2") (pinfunction "DOUT_2") (pintype "output"))
      (node (ref "U32") (pin "4") (pinfunction "DIN_4") (pintype "input"))
    )
    (net (code "35") (name "Net-(U32-DOUT)") (class "Default")
      (node (ref "U32") (pin "2") (pinfunction "DOUT_2") (pintype "output"))
      (node (ref "U33") (pin "4") (pinfunction "DIN_4") (pintype "input"))
    )
    (net (code "36") (name "Net-(U33-DOUT)") (class "Default")
      (node (ref "U33") (pin "2") (pinfunction "DOUT_2") (pintype "output"))
      (node (ref "U34") (pin "4") (pinfunction "DIN_4") (pintype "input"))
    )
    (net (code "37") (name "Net-(U34-DOUT)") (class "Default")
      (node (ref "U34") (pin "2") (pinfunction "DOUT_2") (pintype "output"))
      (node (ref "U35") (pin "4") (pinfunction "DIN_4") (pintype "input"))
    )
    (net (code "38") (name "Net-(U35-DOUT)") (class "Default")
      (node (ref "U35") (pin "2") (pinfunction "DOUT_2") (pintype "output"))
      (node (ref "U36") (pin "4") (pinfunction "DIN_4") (pintype "input"))
    )
    (net (code "39") (name "Net-(U36-DOUT)") (class "Default")
      (node (ref "U36") (pin "2") (pinfunction "DOUT_2") (pintype "output"))
      (node (ref "U37") (pin "4") (pinfunction "DIN_4") (pintype "input"))
    )
    (net (code "40") (name "Net-(U37-DOUT)") (class "Default")
      (node (ref "U37") (pin "2") (pinfunction "DOUT_2") (pintype "output"))
      (node (ref "U38") (pin "4") (pinfunction "DIN_4") (pintype "input"))
    )
    (net (code "41") (name "Net-(U38-DOUT)") (class "Default")
      (node (ref "U38") (pin "2") (pinfunction "DOUT_2") (pintype "output"))
      (node (ref "U39") (pin "4") (pinfunction "DIN_4") (pintype "input"))
    )
    (net (code "42") (name "Net-(U39-DOUT)") (class "Default")
      (node (ref "U39") (pin "2") (pinfunction "DOUT_2") (pintype "output"))
      (node (ref "U40") (pin "4") (pinfunction "DIN_4") (pintype "input"))
    )
    (net (code "43") (name "Net-(U40-DOUT)") (class "Default")
      (node (ref "U40") (pin "2") (pinfunction "DOUT_2") (pintype "output"))
      (node (ref "U41") (pin "4") (pinfunction "DIN_4") (pintype "input"))
    )
    (net (code "44") (name "Net-(U41-DOUT)") (class "Default")
      (node (ref "U41") (pin "2") (pinfunction "DOUT_2") (pintype "output"))
      (node (ref "U42") (pin "4") (pinfunction "DIN_4") (pintype "input"))
    )
    (net (code "45") (name "Net-(U42-DOUT)") (class "Default")
      (node (ref "U42") (pin "2") (pinfunction "DOUT_2") (pintype "output"))
      (node (ref "U43") (pin "4") (pinfunction "DIN_4") (pintype "input"))
    )
    (net (code "46") (name "Net-(U43-DOUT)") (class "Default")
      (node (ref "U43") (pin "2") (pinfunction "DOUT_2") (pintype "output"))
      (node (ref "U44") (pin "4") (pinfunction "DIN_4") (pintype "input"))
    )
    (net (code "47") (name "Net-(U44-DOUT)") (class "Default")
      (node (ref "U44") (pin "2") (pinfunction "DOUT_2") (pintype "output"))
      (node (ref "U45") (pin "4") (pinfunction "DIN_4") (pintype "input"))
    )
    (net (code "48") (name "Net-(U45-DOUT)") (class "Default")
      (node (ref "U45") (pin "2") (pinfunction "DOUT_2") (pintype "output"))
      (node (ref "U46") (pin "4") (pinfunction "DIN_4") (pintype "input"))
    )
    (net (code "49") (name "VCC") (class "Default")
      (node (ref "C0") (pin "1") (pinfunction "1_1") (pintype "passive"))
      (node (ref "C1") (pin "1") (pinfunction "1_1") (pintype "passive"))
      (node (ref "C10") (pin "1") (pinfunction "1_1") (pintype "passive"))
      (node (ref "C11") (pin "1") (pinfunction "1_1") (pintype "passive"))
      (node (ref "C12") (pin "1") (pinfunction "1_1") (pintype "passive"))
      (node (ref "C13") (pin "1") (pinfunction "1_1") (pintype "passive"))
      (node (ref "C14") (pin "1") (pinfunction "1_1") (pintype "passive"))
      (node (ref "C15") (pin "1") (pinfunction "1_1") (pintype "passive"))
      (node (ref "C16") (pin "1") (pinfunction "1_1") (pintype "passive"))
      (node (ref "C17") (pin "1") (pinfunction "1_1") (pintype "passive"))
      (node (ref "C18") (pin "1") (pinfunction "1_1") (pintype "passive"))
      (node (ref "C19") (pin "1") (pinfunction "1_1") (pintype "passive"))
      (node (ref "C2") (pin "1") (pinfunction "1_1") (pintype "passive"))
      (node (ref "C20") (pin "1") (pinfunction "1_1") (pintype "passive"))
      (node (ref "C21") (pin "1") (pinfunction "1_1") (pintype "passive"))
      (node (ref "C22") (pin "1") (pinfunction "1_1") (pintype "passive"))
      (node (ref "C23") (pin "1") (pinfunction "1_1") (pintype "passive"))
      (node (ref "C24") (pin "1") (pinfunction "1_1") (pintype "passive"))
      (node (ref "C25") (pin "1") (pinfunction "1_1") (pintype "passive"))
      (node (ref "C26") (pin "1") (pinfunction "1_1") (pintype "passive"))
      (node (ref "C27") (pin "1") (pinfunction "1_1") (pintype "passive"))
      (node (ref "C28") (pin "1") (pinfunction "1_1") (pintype "passive"))
      (node (ref "C29") (pin "1") (pinfunction "1_1") (pintype "passive"))
      (node (ref "C3") (pin "1") (pinfunction "1_1") (pintype "passive"))
      (node (ref "C30") (pin "1") (pinfunction "1_1") (pintype "passive"))
      (node (ref "C31") (pin "1") (pinfunction "1_1") (pintype "passive"))
      (node (ref "C32") (pin "1") (pinfunction "1_1") (pintype "passive"))
      (node (ref "C33") (pin "1") (pinfunction "1_1") (pintype "passive"))
      (node (ref "C34") (pin "1") (pinfunction "1_1") (pintype "passive"))
      (node (ref "C35") (pin "1") (pinfunction "1_1") (pintype "passive"))
      (node (ref "C36") (pin "1") (pinfunction "1_1") (pintype "passive"))
      (node (ref "C37") (pin "1") (pinfunction "1_1") (pintype "passive"))
      (node (ref "C38") (pin "1") (pinfunction "1_1") (pintype "passive"))
      (node (ref "C39") (pin "1") (pinfunction "1_1") (pintype "passive"))
      (node (ref "C4") (pin "1") (pinfunction "1_1") (pintype "passive"))
      (node (ref "C40") (pin "1") (pinfunction "1_1") (pintype "passive"))
      (node (ref "C41") (pin "1") (pinfunction "1_1") (pintype "passive"))
      (node (ref "C42") (pin "1") (pinfunction "1_1") (pintype "passive"))
      (node (ref "C43") (pin "1") (pinfunction "1_1") (pintype "passive"))
      (node (ref "C44") (pin "1") (pinfunction "1_1") (pintype "passive"))
      (node (ref "C45") (pin "1") (pinfunction "1_1") (pintype "passive"))
      (node (ref "C46") (pin "1") (pinfunction "1_1") (pintype "passive"))
      (node (ref "C5") (pin "1") (pinfunction "1_1") (pintype "passive"))
      (node (ref "C6") (pin "1") (pinfunction "1_1") (pintype "passive"))
      (node (ref "C7") (pin "1") (pinfunction "1_1") (pintype "passive"))
      (node (ref "C8") (pin "1") (pinfunction "1_1") (pintype "passive"))
      (node (ref "C9") (pin "1") (pinfunction "1_1") (pintype "passive"))
      (node (ref "J1") (pin "1") (pinfunction "1_1") (pintype "passive"))
      (node (ref "U0") (pin "1") (pinfunction "VDD_1") (pintype "power_in"))
      (node (ref "U1") (pin "1") (pinfunction "VDD_1") (pintype "power_in"))
      (node (ref "U10") (pin "1") (pinfunction "VDD_1") (pintype "power_in"))
      (node (ref "U11") (pin "1") (pinfunction "VDD_1") (pintype "power_in"))
      (node (ref "U12") (pin "1") (pinfunction "VDD_1") (pintype "power_in"))
      (node (ref "U13") (pin "1") (pinfunction "VDD_1") (pintype "power_in"))
      (node (ref "U14") (pin "1") (pinfunction "VDD_1") (pintype "power_in"))
      (node (ref "U15") (pin "1") (pinfunction "VDD_1") (pintype "power_in"))
      (node (ref "U16") (pin "1") (pinfunction "VDD_1") (pintype "power_in"))
      (node (ref "U17") (pin "1") (pinfunction "VDD_1") (pintype "power_in"))
      (node (ref "U18") (pin "1") (pinfunction "VDD_1") (pintype "power_in"))
      (node (ref "U19") (pin "1") (pinfunction "VDD_1") (pintype "power_in"))
      (node (ref "U2") (pin "1") (pinfunction "VDD_1") (pintype "power_in"))
      (node (ref "U20") (pin "1") (pinfunction "VDD_1") (pintype "power_in"))
      (node (ref "U21") (pin "1") (pinfunction "VDD_1") (pintype "power_in"))
      (node (ref "U22") (pin "1") (pinfunction "VDD_1") (pintype "power_in"))
      (node (ref "U23") (pin "1") (pinfunction "VDD_1") (pintype "power_in"))
      (node (ref "U24") (pin "1") (pinfunction "VDD_1") (pintype "power_in"))
      (node (ref "U25") (pin "1") (pinfunction "VDD_1") (pintype "power_in"))
      (node (ref "U26") (pin "1") (pinfunction "VDD_1") (pintype "power_in"))
      (node (ref "U27") (pin "1") (pinfunction "VDD_1") (pintype "power_in"))
      (node (ref "U28") (pin "1") (pinfunction "VDD_1") (pintype "power_in"))
      (node (ref "U29") (pin "1") (pinfunction "VDD_1") (pintype "power_in"))
      (node (ref "U3") (pin "1") (pinfunction "VDD_1") (pintype "power_in"))
      (node (ref "U30") (pin "1") (pinfunction "VDD_1") (pintype "power_in"))
      (node (ref "U31") (pin "1") (pinfunction "VDD_1") (pintype "power_in"))
      (node (ref "U32") (pin "1") (pinfunction "VDD_1") (pintype "power_in"))
      (node (ref "U33") (pin "1") (pinfunction "VDD_1") (pintype "power_in"))
      (node (ref "U34") (pin "1") (pinfunction "VDD_1") (pintype "power_in"))
      (node (ref "U35") (pin "1") (pinfunction "VDD_1") (pintype "power_in"))
      (node (ref "U36") (pin "1") (pinfunction "VDD_1") (pintype "power_in"))
      (node (ref "U37") (pin "1") (pinfunction "VDD_1") (pintype "power_in"))
      (node (ref "U38") (pin "1") (pinfunction "VDD_1") (pintype "power_in"))
      (node (ref "U39") (pin "1") (pinfunction "VDD_1") (pintype "power_in"))
      (node (ref "U4") (pin "1") (pinfunction "VDD_1") (pintype "power_in"))
      (node (ref "U40") (pin "1") (pinfunction "VDD_1") (pintype "power_in"))
      (node (ref "U41") (pin "1") (pinfunction "VDD_1") (pintype "power_in"))
      (node (ref "U42") (pin "1") (pinfunction "VDD_1") (pintype "power_in"))
      (node (ref "U43") (pin "1") (pinfunction "VDD_1") (pintype "power_in"))
      (node (ref "U44") (pin "1") (pinfunction "VDD_1") (pintype "power_in"))
      (node (ref "U45") (pin "1") (pinfunction "VDD_1") (pintype "power_in"))
      (node (ref "U46") (pin "1") (pinfunction "VDD_1") (pintype "power_in"))
      (node (ref "U5") (pin "1") (pinfunction "VDD_1") (pintype "power_in"))
      (node (ref "U6") (pin "1") (pinfunction "VDD_1") (pintype "power_in"))
      (node (ref "U7") (pin "1") (pinfunction "VDD_1") (pintype "power_in"))
      (node (ref "U8") (pin "1") (pinfunction "VDD_1") (pintype "power_in"))
      (node (ref "U9") (pin "1") (pinfunction "VDD_1") (pintype "power_in"))
    )
    (net (code "50") (name "unconnected-(J1-MNT_1-Pad4)") (class "Default")
      (node (ref "J1") (pin "4") (pinfunction "MNT_1_4") (pintype "passive+no_connect"))
    )
    (net (code "51") (name "unconnected-(J1-MNT_2-Pad5)") (class "Default")
      (node (ref "J1") (pin "5") (pinfunction "MNT_2_5") (pintype "passive+no_connect"))
    )
    (net (code "52") (name "unconnected-(U46-DOUT-Pad2)") (class "Default")
      (node (ref "U46") (pin "2") (pinfunction "DOUT_2") (pintype "output+no_connect"))
    )
  )
)
